# 04-Front_Panel_SFP.net
KiCad netlist of a schematic drawn in Altium Designer
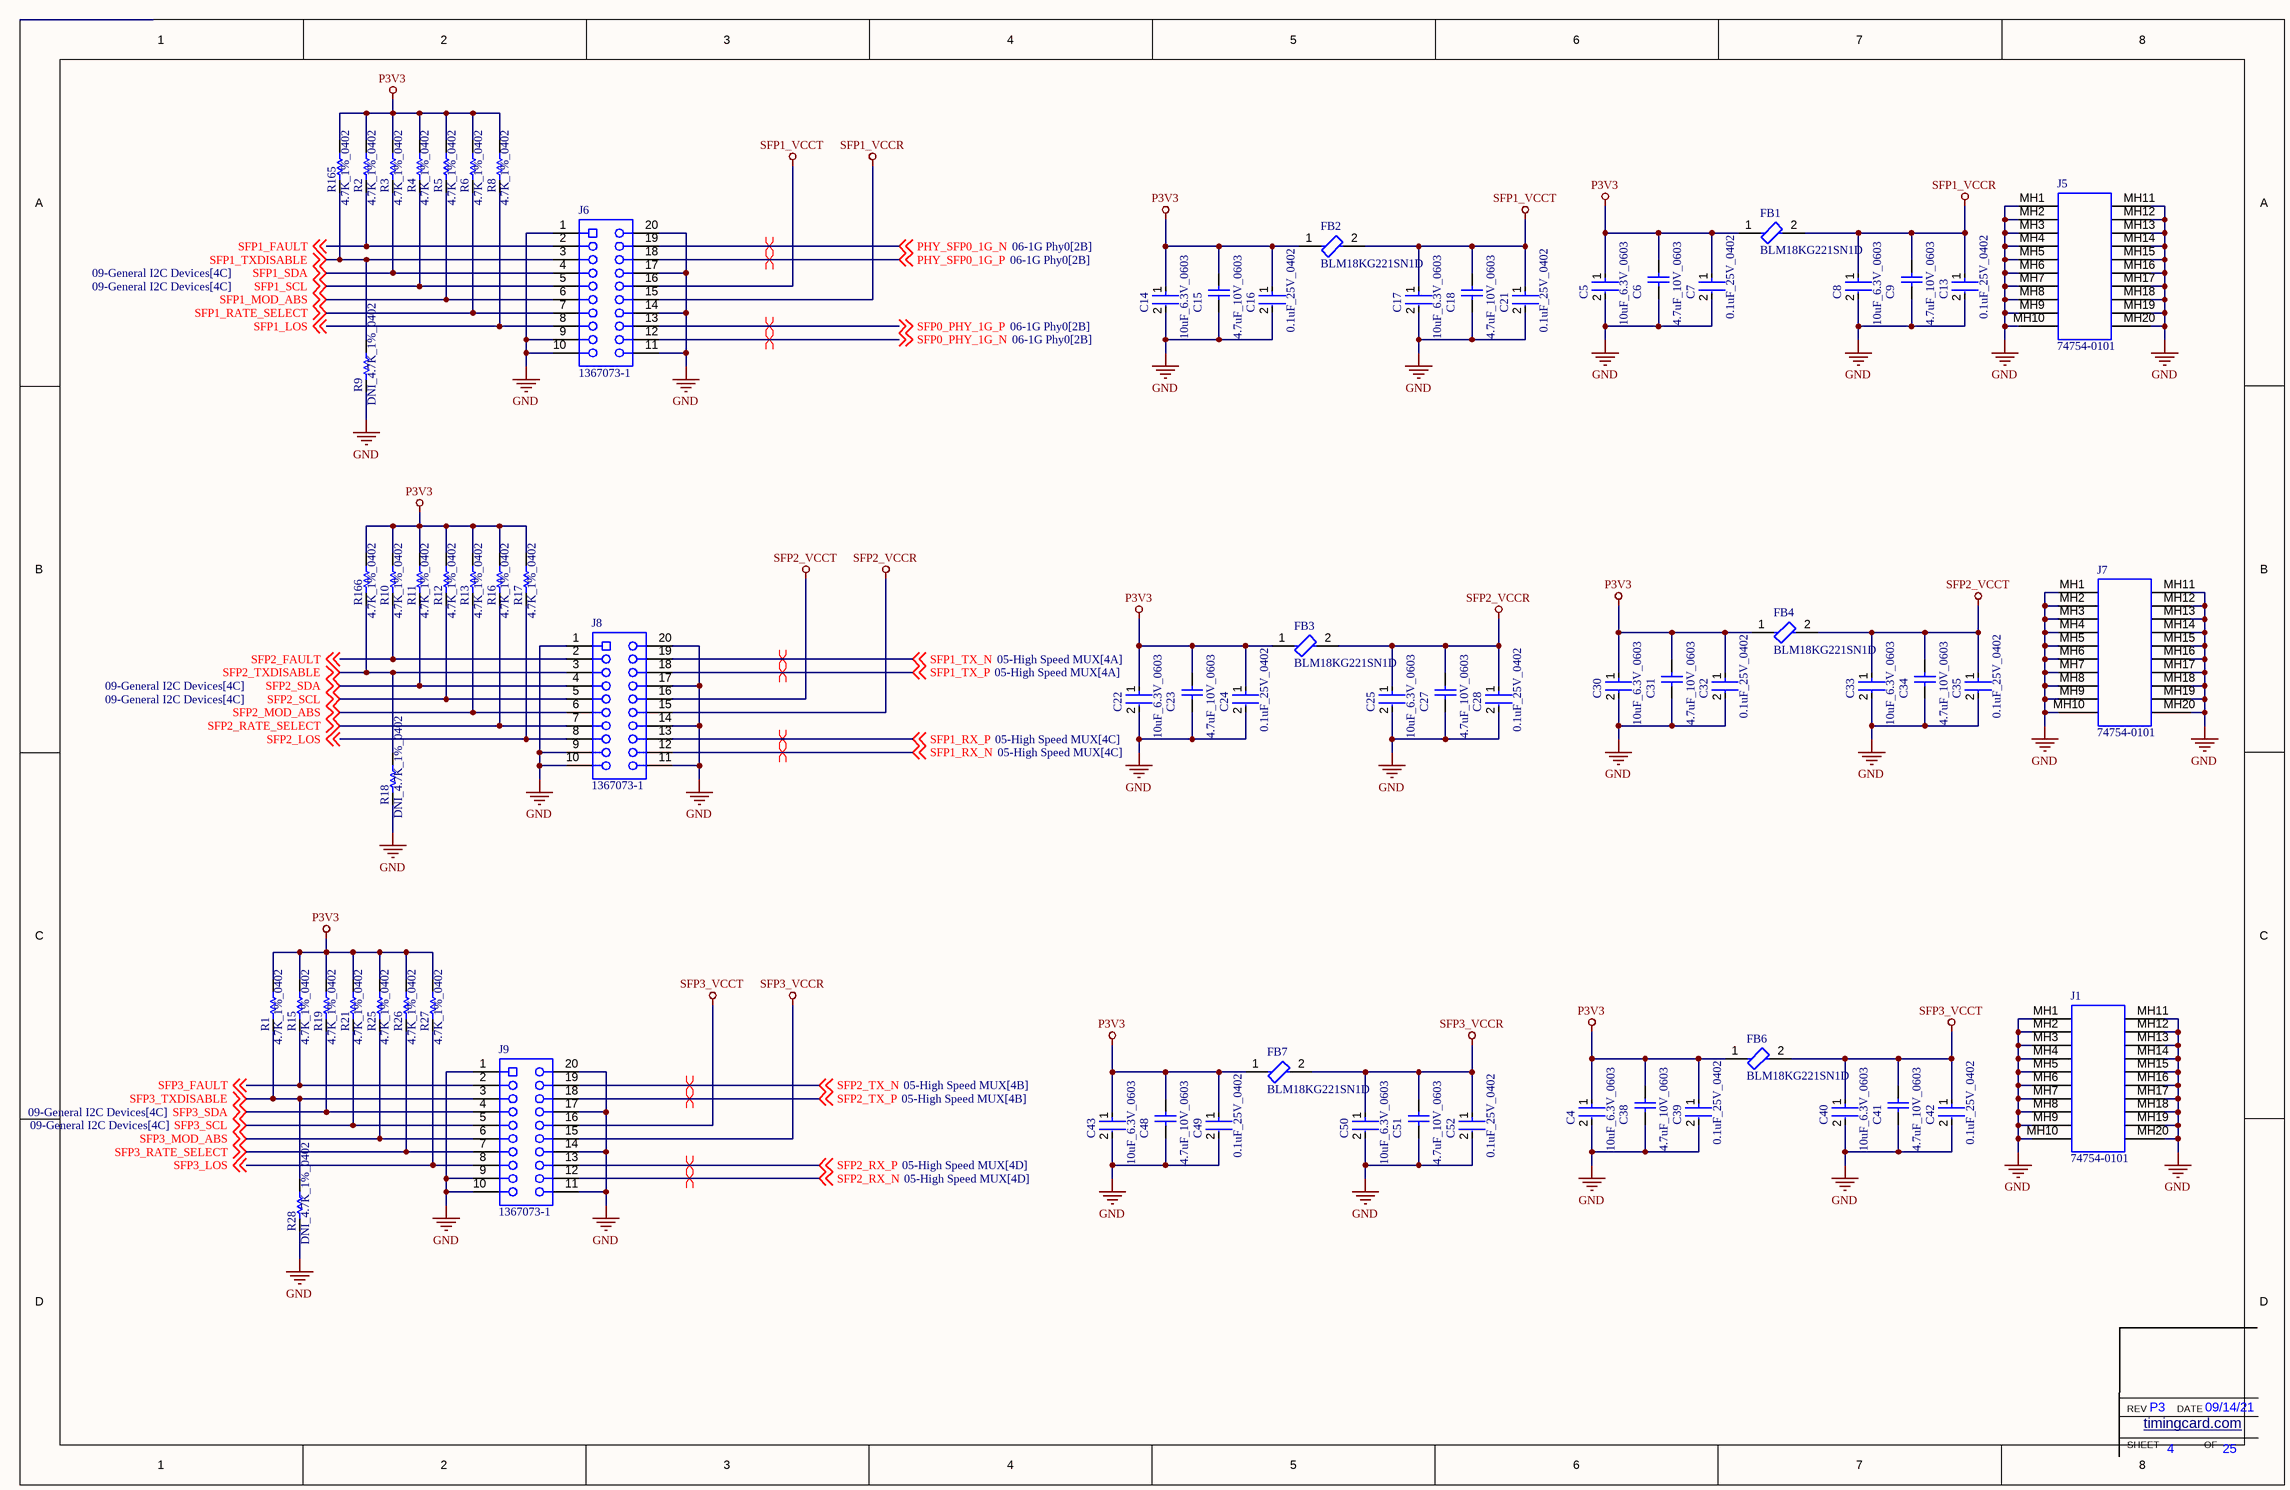
[diagram p0: 04-Front Panel SFP+.SchDoc]

(export (version "E")
  (design (tool "Eeschema 10.0.6"))
  (components
    (comp (ref "C4")
      (value "10uF_6.3V_0603")
      (footprint "FP-C0603C106M9PACTU-MFG")
      (description "CAP CER 10UF 6.3V X5R 0603")
      (fields
        (field (name "MANUFACTURER PART NUMBER") "C0603C106M9PACTU")
        (field (name "MANUFACTURER") "Kemet")
      )
      (libsource (lib "Altium Content Vault") (part "b4654b650e69147ec39a6b967a45e02"))
    )
    (comp (ref "C5")
      (value "10uF_6.3V_0603")
      (footprint "FP-C0603C106M9PACTU-MFG")
      (description "CAP CER 10UF 6.3V X5R 0603")
      (fields
        (field (name "MANUFACTURER PART NUMBER") "C0603C106M9PACTU")
        (field (name "MANUFACTURER") "Kemet")
      )
      (libsource (lib "Altium Content Vault") (part "b4654b650e69147ec39a6b967a45e02"))
    )
    (comp (ref "C6")
      (value "4.7uF_10V_0603")
      (footprint "CAPC1608X87X35NL15T15")
      (fields (field (name "PART NUMBER") "C0603C475K8PACTU") (field (name "MANUFACTURER") "Kemet"))
      (libsource (lib "Altium Content Vault") (part "CAP"))
    )
    (comp (ref "C7")
      (value "0.1uF_25V_0402")
      (footprint "FP-0402-L_1_0_1-W_0_5_0_1-IPC_C")
      (description "General Purpose Ceramic Capacitor, 0402, 100nF, 10%, X7R, 15%, 25V")
      (fields (field (name "VOLTAGE") "25V") (field (name "TOLERANCE") "10%"))
      (libsource (lib "Altium Content Vault") (part "b4654b650e69147ec39a6b967a45e02"))
    )
    (comp (ref "C8")
      (value "10uF_6.3V_0603")
      (footprint "FP-C0603C106M9PACTU-MFG")
      (description "CAP CER 10UF 6.3V X5R 0603")
      (fields
        (field (name "MANUFACTURER PART NUMBER") "C0603C106M9PACTU")
        (field (name "MANUFACTURER") "Kemet")
      )
      (libsource (lib "Altium Content Vault") (part "b4654b650e69147ec39a6b967a45e02"))
    )
    (comp (ref "C9")
      (value "4.7uF_10V_0603")
      (footprint "CAPC1608X87X35NL15T15")
      (fields (field (name "PART NUMBER") "C0603C475K8PACTU") (field (name "MANUFACTURER") "Kemet"))
      (libsource (lib "Altium Content Vault") (part "CAP"))
    )
    (comp (ref "C13")
      (value "0.1uF_25V_0402")
      (footprint "FP-0402-L_1_0_1-W_0_5_0_1-IPC_C")
      (description "General Purpose Ceramic Capacitor, 0402, 100nF, 10%, X7R, 15%, 25V")
      (fields (field (name "VOLTAGE") "25V") (field (name "TOLERANCE") "10%"))
      (libsource (lib "Altium Content Vault") (part "b4654b650e69147ec39a6b967a45e02"))
    )
    (comp (ref "C14")
      (value "10uF_6.3V_0603")
      (footprint "FP-C0603C106M9PACTU-MFG")
      (description "CAP CER 10UF 6.3V X5R 0603")
      (fields
        (field (name "MANUFACTURER PART NUMBER") "C0603C106M9PACTU")
        (field (name "MANUFACTURER") "Kemet")
      )
      (libsource (lib "Altium Content Vault") (part "b4654b650e69147ec39a6b967a45e02"))
    )
    (comp (ref "C15")
      (value "4.7uF_10V_0603")
      (footprint "CAPC1608X87X35NL15T15")
      (fields (field (name "PART NUMBER") "C0603C475K8PACTU") (field (name "MANUFACTURER") "Kemet"))
      (libsource (lib "Altium Content Vault") (part "CAP"))
    )
    (comp (ref "C16")
      (value "0.1uF_25V_0402")
      (footprint "FP-0402-L_1_0_1-W_0_5_0_1-IPC_C")
      (description "General Purpose Ceramic Capacitor, 0402, 100nF, 10%, X7R, 15%, 25V")
      (fields (field (name "VOLTAGE") "25V") (field (name "TOLERANCE") "10%"))
      (libsource (lib "Altium Content Vault") (part "b4654b650e69147ec39a6b967a45e02"))
    )
    (comp (ref "C17")
      (value "10uF_6.3V_0603")
      (footprint "FP-C0603C106M9PACTU-MFG")
      (description "CAP CER 10UF 6.3V X5R 0603")
      (fields
        (field (name "MANUFACTURER PART NUMBER") "C0603C106M9PACTU")
        (field (name "MANUFACTURER") "Kemet")
      )
      (libsource (lib "Altium Content Vault") (part "b4654b650e69147ec39a6b967a45e02"))
    )
    (comp (ref "C18")
      (value "4.7uF_10V_0603")
      (footprint "CAPC1608X87X35NL15T15")
      (fields (field (name "PART NUMBER") "C0603C475K8PACTU") (field (name "MANUFACTURER") "Kemet"))
      (libsource (lib "Altium Content Vault") (part "CAP"))
    )
    (comp (ref "C21")
      (value "0.1uF_25V_0402")
      (footprint "FP-0402-L_1_0_1-W_0_5_0_1-IPC_C")
      (description "General Purpose Ceramic Capacitor, 0402, 100nF, 10%, X7R, 15%, 25V")
      (fields (field (name "VOLTAGE") "25V") (field (name "TOLERANCE") "10%"))
      (libsource (lib "Altium Content Vault") (part "b4654b650e69147ec39a6b967a45e02"))
    )
    (comp (ref "C22")
      (value "10uF_6.3V_0603")
      (footprint "FP-C0603C106M9PACTU-MFG")
      (description "CAP CER 10UF 6.3V X5R 0603")
      (fields
        (field (name "MANUFACTURER PART NUMBER") "C0603C106M9PACTU")
        (field (name "MANUFACTURER") "Kemet")
      )
      (libsource (lib "Altium Content Vault") (part "b4654b650e69147ec39a6b967a45e02"))
    )
    (comp (ref "C23")
      (value "4.7uF_10V_0603")
      (footprint "CAPC1608X87X35NL15T15")
      (fields (field (name "PART NUMBER") "C0603C475K8PACTU") (field (name "MANUFACTURER") "Kemet"))
      (libsource (lib "Altium Content Vault") (part "CAP"))
    )
    (comp (ref "C24")
      (value "0.1uF_25V_0402")
      (footprint "FP-0402-L_1_0_1-W_0_5_0_1-IPC_C")
      (description "General Purpose Ceramic Capacitor, 0402, 100nF, 10%, X7R, 15%, 25V")
      (fields (field (name "VOLTAGE") "25V") (field (name "TOLERANCE") "10%"))
      (libsource (lib "Altium Content Vault") (part "b4654b650e69147ec39a6b967a45e02"))
    )
    (comp (ref "C25")
      (value "10uF_6.3V_0603")
      (footprint "FP-C0603C106M9PACTU-MFG")
      (description "CAP CER 10UF 6.3V X5R 0603")
      (fields
        (field (name "MANUFACTURER PART NUMBER") "C0603C106M9PACTU")
        (field (name "MANUFACTURER") "Kemet")
      )
      (libsource (lib "Altium Content Vault") (part "b4654b650e69147ec39a6b967a45e02"))
    )
    (comp (ref "C27")
      (value "4.7uF_10V_0603")
      (footprint "CAPC1608X87X35NL15T15")
      (fields (field (name "PART NUMBER") "C0603C475K8PACTU") (field (name "MANUFACTURER") "Kemet"))
      (libsource (lib "Altium Content Vault") (part "CAP"))
    )
    (comp (ref "C28")
      (value "0.1uF_25V_0402")
      (footprint "FP-0402-L_1_0_1-W_0_5_0_1-IPC_C")
      (description "General Purpose Ceramic Capacitor, 0402, 100nF, 10%, X7R, 15%, 25V")
      (fields (field (name "VOLTAGE") "25V") (field (name "TOLERANCE") "10%"))
      (libsource (lib "Altium Content Vault") (part "b4654b650e69147ec39a6b967a45e02"))
    )
    (comp (ref "C30")
      (value "10uF_6.3V_0603")
      (footprint "FP-C0603C106M9PACTU-MFG")
      (description "CAP CER 10UF 6.3V X5R 0603")
      (fields
        (field (name "MANUFACTURER PART NUMBER") "C0603C106M9PACTU")
        (field (name "MANUFACTURER") "Kemet")
      )
      (libsource (lib "Altium Content Vault") (part "b4654b650e69147ec39a6b967a45e02"))
    )
    (comp (ref "C31")
      (value "4.7uF_10V_0603")
      (footprint "CAPC1608X87X35NL15T15")
      (fields (field (name "PART NUMBER") "C0603C475K8PACTU") (field (name "MANUFACTURER") "Kemet"))
      (libsource (lib "Altium Content Vault") (part "CAP"))
    )
    (comp (ref "C32")
      (value "0.1uF_25V_0402")
      (footprint "FP-0402-L_1_0_1-W_0_5_0_1-IPC_C")
      (description "General Purpose Ceramic Capacitor, 0402, 100nF, 10%, X7R, 15%, 25V")
      (fields (field (name "VOLTAGE") "25V") (field (name "TOLERANCE") "10%"))
      (libsource (lib "Altium Content Vault") (part "b4654b650e69147ec39a6b967a45e02"))
    )
    (comp (ref "C33")
      (value "10uF_6.3V_0603")
      (footprint "FP-C0603C106M9PACTU-MFG")
      (description "CAP CER 10UF 6.3V X5R 0603")
      (fields
        (field (name "MANUFACTURER PART NUMBER") "C0603C106M9PACTU")
        (field (name "MANUFACTURER") "Kemet")
      )
      (libsource (lib "Altium Content Vault") (part "b4654b650e69147ec39a6b967a45e02"))
    )
    (comp (ref "C34")
      (value "4.7uF_10V_0603")
      (footprint "CAPC1608X87X35NL15T15")
      (fields (field (name "PART NUMBER") "C0603C475K8PACTU") (field (name "MANUFACTURER") "Kemet"))
      (libsource (lib "Altium Content Vault") (part "CAP"))
    )
    (comp (ref "C35")
      (value "0.1uF_25V_0402")
      (footprint "FP-0402-L_1_0_1-W_0_5_0_1-IPC_C")
      (description "General Purpose Ceramic Capacitor, 0402, 100nF, 10%, X7R, 15%, 25V")
      (fields (field (name "VOLTAGE") "25V") (field (name "TOLERANCE") "10%"))
      (libsource (lib "Altium Content Vault") (part "b4654b650e69147ec39a6b967a45e02"))
    )
    (comp (ref "C38")
      (value "4.7uF_10V_0603")
      (footprint "CAPC1608X87X35NL15T15")
      (fields (field (name "PART NUMBER") "C0603C475K8PACTU") (field (name "MANUFACTURER") "Kemet"))
      (libsource (lib "Altium Content Vault") (part "CAP"))
    )
    (comp (ref "C39")
      (value "0.1uF_25V_0402")
      (footprint "FP-0402-L_1_0_1-W_0_5_0_1-IPC_C")
      (description "General Purpose Ceramic Capacitor, 0402, 100nF, 10%, X7R, 15%, 25V")
      (fields (field (name "VOLTAGE") "25V") (field (name "TOLERANCE") "10%"))
      (libsource (lib "Altium Content Vault") (part "b4654b650e69147ec39a6b967a45e02"))
    )
    (comp (ref "C40")
      (value "10uF_6.3V_0603")
      (footprint "FP-C0603C106M9PACTU-MFG")
      (description "CAP CER 10UF 6.3V X5R 0603")
      (fields
        (field (name "MANUFACTURER PART NUMBER") "C0603C106M9PACTU")
        (field (name "MANUFACTURER") "Kemet")
      )
      (libsource (lib "Altium Content Vault") (part "b4654b650e69147ec39a6b967a45e02"))
    )
    (comp (ref "C41")
      (value "4.7uF_10V_0603")
      (footprint "CAPC1608X87X35NL15T15")
      (fields (field (name "PART NUMBER") "C0603C475K8PACTU") (field (name "MANUFACTURER") "Kemet"))
      (libsource (lib "Altium Content Vault") (part "CAP"))
    )
    (comp (ref "C42")
      (value "0.1uF_25V_0402")
      (footprint "FP-0402-L_1_0_1-W_0_5_0_1-IPC_C")
      (description "General Purpose Ceramic Capacitor, 0402, 100nF, 10%, X7R, 15%, 25V")
      (fields (field (name "VOLTAGE") "25V") (field (name "TOLERANCE") "10%"))
      (libsource (lib "Altium Content Vault") (part "b4654b650e69147ec39a6b967a45e02"))
    )
    (comp (ref "C43")
      (value "10uF_6.3V_0603")
      (footprint "FP-C0603C106M9PACTU-MFG")
      (description "CAP CER 10UF 6.3V X5R 0603")
      (fields
        (field (name "MANUFACTURER PART NUMBER") "C0603C106M9PACTU")
        (field (name "MANUFACTURER") "Kemet")
      )
      (libsource (lib "Altium Content Vault") (part "b4654b650e69147ec39a6b967a45e02"))
    )
    (comp (ref "C48")
      (value "4.7uF_10V_0603")
      (footprint "CAPC1608X87X35NL15T15")
      (fields (field (name "PART NUMBER") "C0603C475K8PACTU") (field (name "MANUFACTURER") "Kemet"))
      (libsource (lib "Altium Content Vault") (part "CAP"))
    )
    (comp (ref "C49")
      (value "0.1uF_25V_0402")
      (footprint "FP-0402-L_1_0_1-W_0_5_0_1-IPC_C")
      (description "General Purpose Ceramic Capacitor, 0402, 100nF, 10%, X7R, 15%, 25V")
      (fields (field (name "VOLTAGE") "25V") (field (name "TOLERANCE") "10%"))
      (libsource (lib "Altium Content Vault") (part "b4654b650e69147ec39a6b967a45e02"))
    )
    (comp (ref "C50")
      (value "10uF_6.3V_0603")
      (footprint "FP-C0603C106M9PACTU-MFG")
      (description "CAP CER 10UF 6.3V X5R 0603")
      (fields
        (field (name "MANUFACTURER PART NUMBER") "C0603C106M9PACTU")
        (field (name "MANUFACTURER") "Kemet")
      )
      (libsource (lib "Altium Content Vault") (part "b4654b650e69147ec39a6b967a45e02"))
    )
    (comp (ref "C51")
      (value "4.7uF_10V_0603")
      (footprint "CAPC1608X87X35NL15T15")
      (fields (field (name "PART NUMBER") "C0603C475K8PACTU") (field (name "MANUFACTURER") "Kemet"))
      (libsource (lib "Altium Content Vault") (part "CAP"))
    )
    (comp (ref "C52")
      (value "0.1uF_25V_0402")
      (footprint "FP-0402-L_1_0_1-W_0_5_0_1-IPC_C")
      (description "General Purpose Ceramic Capacitor, 0402, 100nF, 10%, X7R, 15%, 25V")
      (fields (field (name "VOLTAGE") "25V") (field (name "TOLERANCE") "10%"))
      (libsource (lib "Altium Content Vault") (part "b4654b650e69147ec39a6b967a45e02"))
    )
    (comp (ref "FB1")
      (value "BLM18KG221SN1D")
      (footprint "FP-BLM18-0_15-t0_8-IPC_B")
      (description "Chip Ferrite Bead, 0603, 220Ω @ 100MHz, 0.05Ω, 25%, 2.2A")
      (fields (field (name "TOLERANCE") "25%"))
      (libsource (lib "Altium Content Vault") (part "5f30dd21d616792df468990f7003faa"))
    )
    (comp (ref "FB2")
      (value "BLM18KG221SN1D")
      (footprint "FP-BLM18-0_15-t0_8-IPC_B")
      (description "Chip Ferrite Bead, 0603, 220Ω @ 100MHz, 0.05Ω, 25%, 2.2A")
      (fields (field (name "TOLERANCE") "25%"))
      (libsource (lib "Altium Content Vault") (part "5f30dd21d616792df468990f7003faa"))
    )
    (comp (ref "FB3")
      (value "BLM18KG221SN1D")
      (footprint "FP-BLM18-0_15-t0_8-IPC_B")
      (description "Chip Ferrite Bead, 0603, 220Ω @ 100MHz, 0.05Ω, 25%, 2.2A")
      (fields (field (name "TOLERANCE") "25%"))
      (libsource (lib "Altium Content Vault") (part "5f30dd21d616792df468990f7003faa"))
    )
    (comp (ref "FB4")
      (value "BLM18KG221SN1D")
      (footprint "FP-BLM18-0_15-t0_8-IPC_B")
      (description "Chip Ferrite Bead, 0603, 220Ω @ 100MHz, 0.05Ω, 25%, 2.2A")
      (fields (field (name "TOLERANCE") "25%"))
      (libsource (lib "Altium Content Vault") (part "5f30dd21d616792df468990f7003faa"))
    )
    (comp (ref "FB6")
      (value "BLM18KG221SN1D")
      (footprint "FP-BLM18-0_15-t0_8-IPC_B")
      (description "Chip Ferrite Bead, 0603, 220Ω @ 100MHz, 0.05Ω, 25%, 2.2A")
      (fields (field (name "TOLERANCE") "25%"))
      (libsource (lib "Altium Content Vault") (part "5f30dd21d616792df468990f7003faa"))
    )
    (comp (ref "FB7")
      (value "BLM18KG221SN1D")
      (footprint "FP-BLM18-0_15-t0_8-IPC_B")
      (description "Chip Ferrite Bead, 0603, 220Ω @ 100MHz, 0.05Ω, 25%, 2.2A")
      (fields (field (name "TOLERANCE") "25%"))
      (libsource (lib "Altium Content Vault") (part "5f30dd21d616792df468990f7003faa"))
    )
    (comp (ref "J1")
      (value "74754-0101")
      (footprint "MOLX-74754-0101_V")
      (description "SFP+ Cage, Single Port, Height 10.85 mm, Tail Height 3.05 mm, -40 to 85 degC, RoHS, Tray")
      (libsource (lib "Altium Content Vault") (part "MOLX-74754-0101"))
    )
    (comp (ref "J5")
      (value "74754-0101")
      (footprint "MOLX-74754-0101_V")
      (description "SFP+ Cage, Single Port, Height 10.85 mm, Tail Height 3.05 mm, -40 to 85 degC, RoHS, Tray")
      (libsource (lib "Altium Content Vault") (part "MOLX-74754-0101"))
    )
    (comp (ref "J6")
      (value "1367073-1")
      (footprint "TECO-1367073-1_V")
      (fields (field (name "MANUFACTURER") "TE Connectivity"))
      (libsource (lib "Altium Content Vault") (part "CN-2P-F-R20_B"))
    )
    (comp (ref "J7")
      (value "74754-0101")
      (footprint "MOLX-74754-0101_V")
      (description "SFP+ Cage, Single Port, Height 10.85 mm, Tail Height 3.05 mm, -40 to 85 degC, RoHS, Tray")
      (libsource (lib "Altium Content Vault") (part "MOLX-74754-0101"))
    )
    (comp (ref "J8")
      (value "1367073-1")
      (footprint "TECO-1367073-1_V")
      (fields (field (name "MANUFACTURER") "TE Connectivity"))
      (libsource (lib "Altium Content Vault") (part "CN-2P-F-R20_B"))
    )
    (comp (ref "J9")
      (value "1367073-1")
      (footprint "TECO-1367073-1_V")
      (fields (field (name "MANUFACTURER") "TE Connectivity"))
      (libsource (lib "Altium Content Vault") (part "CN-2P-F-R20_B"))
    )
    (comp (ref "R1")
      (value "4.7K_1%_0402")
      (footprint "RESC1005X40X25NL10T10")
      (fields (field (name "MANUFACTURER") "Bourns") (field (name "PART NUMBER") "CR0402-FX-4701GLF"))
      (libsource (lib "Altium Content Vault") (part "RES"))
    )
    (comp (ref "R2")
      (value "4.7K_1%_0402")
      (footprint "RESC1005X40X25NL10T10")
      (fields (field (name "MANUFACTURER") "Bourns") (field (name "PART NUMBER") "CR0402-FX-4701GLF"))
      (libsource (lib "Altium Content Vault") (part "RES"))
    )
    (comp (ref "R3")
      (value "4.7K_1%_0402")
      (footprint "RESC1005X40X25NL10T10")
      (fields (field (name "MANUFACTURER") "Bourns") (field (name "PART NUMBER") "CR0402-FX-4701GLF"))
      (libsource (lib "Altium Content Vault") (part "RES"))
    )
    (comp (ref "R4")
      (value "4.7K_1%_0402")
      (footprint "RESC1005X40X25NL10T10")
      (fields (field (name "MANUFACTURER") "Bourns") (field (name "PART NUMBER") "CR0402-FX-4701GLF"))
      (libsource (lib "Altium Content Vault") (part "RES"))
    )
    (comp (ref "R5")
      (value "4.7K_1%_0402")
      (footprint "RESC1005X40X25NL10T10")
      (fields (field (name "MANUFACTURER") "Bourns") (field (name "PART NUMBER") "CR0402-FX-4701GLF"))
      (libsource (lib "Altium Content Vault") (part "RES"))
    )
    (comp (ref "R6")
      (value "4.7K_1%_0402")
      (footprint "RESC1005X40X25NL10T10")
      (fields (field (name "MANUFACTURER") "Bourns") (field (name "PART NUMBER") "CR0402-FX-4701GLF"))
      (libsource (lib "Altium Content Vault") (part "RES"))
    )
    (comp (ref "R8")
      (value "4.7K_1%_0402")
      (footprint "RESC1005X40X25NL10T10")
      (fields (field (name "MANUFACTURER") "Bourns") (field (name "PART NUMBER") "CR0402-FX-4701GLF"))
      (libsource (lib "Altium Content Vault") (part "RES"))
    )
    (comp (ref "R9")
      (value "DNI_4.7K_1%_0402")
      (footprint "RESC1005X40X25NL10T10")
      (fields (field (name "MANUFACTURER") "Bourns") (field (name "PART NUMBER") "CR0402-FX-4701GLF"))
      (libsource (lib "Altium Content Vault") (part "RES"))
    )
    (comp (ref "R10")
      (value "4.7K_1%_0402")
      (footprint "RESC1005X40X25NL10T10")
      (fields (field (name "MANUFACTURER") "Bourns") (field (name "PART NUMBER") "CR0402-FX-4701GLF"))
      (libsource (lib "Altium Content Vault") (part "RES"))
    )
    (comp (ref "R11")
      (value "4.7K_1%_0402")
      (footprint "RESC1005X40X25NL10T10")
      (fields (field (name "MANUFACTURER") "Bourns") (field (name "PART NUMBER") "CR0402-FX-4701GLF"))
      (libsource (lib "Altium Content Vault") (part "RES"))
    )
    (comp (ref "R12")
      (value "4.7K_1%_0402")
      (footprint "RESC1005X40X25NL10T10")
      (fields (field (name "MANUFACTURER") "Bourns") (field (name "PART NUMBER") "CR0402-FX-4701GLF"))
      (libsource (lib "Altium Content Vault") (part "RES"))
    )
    (comp (ref "R13")
      (value "4.7K_1%_0402")
      (footprint "RESC1005X40X25NL10T10")
      (fields (field (name "MANUFACTURER") "Bourns") (field (name "PART NUMBER") "CR0402-FX-4701GLF"))
      (libsource (lib "Altium Content Vault") (part "RES"))
    )
    (comp (ref "R15")
      (value "4.7K_1%_0402")
      (footprint "RESC1005X40X25NL10T10")
      (fields (field (name "MANUFACTURER") "Bourns") (field (name "PART NUMBER") "CR0402-FX-4701GLF"))
      (libsource (lib "Altium Content Vault") (part "RES"))
    )
    (comp (ref "R16")
      (value "4.7K_1%_0402")
      (footprint "RESC1005X40X25NL10T10")
      (fields (field (name "MANUFACTURER") "Bourns") (field (name "PART NUMBER") "CR0402-FX-4701GLF"))
      (libsource (lib "Altium Content Vault") (part "RES"))
    )
    (comp (ref "R17")
      (value "4.7K_1%_0402")
      (footprint "RESC1005X40X25NL10T10")
      (fields (field (name "MANUFACTURER") "Bourns") (field (name "PART NUMBER") "CR0402-FX-4701GLF"))
      (libsource (lib "Altium Content Vault") (part "RES"))
    )
    (comp (ref "R18")
      (value "DNI_4.7K_1%_0402")
      (footprint "RESC1005X40X25NL10T10")
      (fields (field (name "MANUFACTURER") "Bourns") (field (name "PART NUMBER") "CR0402-FX-4701GLF"))
      (libsource (lib "Altium Content Vault") (part "RES"))
    )
    (comp (ref "R19")
      (value "4.7K_1%_0402")
      (footprint "RESC1005X40X25NL10T10")
      (fields (field (name "MANUFACTURER") "Bourns") (field (name "PART NUMBER") "CR0402-FX-4701GLF"))
      (libsource (lib "Altium Content Vault") (part "RES"))
    )
    (comp (ref "R21")
      (value "4.7K_1%_0402")
      (footprint "RESC1005X40X25NL10T10")
      (fields (field (name "MANUFACTURER") "Bourns") (field (name "PART NUMBER") "CR0402-FX-4701GLF"))
      (libsource (lib "Altium Content Vault") (part "RES"))
    )
    (comp (ref "R25")
      (value "4.7K_1%_0402")
      (footprint "RESC1005X40X25NL10T10")
      (fields (field (name "MANUFACTURER") "Bourns") (field (name "PART NUMBER") "CR0402-FX-4701GLF"))
      (libsource (lib "Altium Content Vault") (part "RES"))
    )
    (comp (ref "R26")
      (value "4.7K_1%_0402")
      (footprint "RESC1005X40X25NL10T10")
      (fields (field (name "MANUFACTURER") "Bourns") (field (name "PART NUMBER") "CR0402-FX-4701GLF"))
      (libsource (lib "Altium Content Vault") (part "RES"))
    )
    (comp (ref "R27")
      (value "4.7K_1%_0402")
      (footprint "RESC1005X40X25NL10T10")
      (fields (field (name "MANUFACTURER") "Bourns") (field (name "PART NUMBER") "CR0402-FX-4701GLF"))
      (libsource (lib "Altium Content Vault") (part "RES"))
    )
    (comp (ref "R28")
      (value "DNI_4.7K_1%_0402")
      (footprint "RESC1005X40X25NL10T10")
      (fields (field (name "MANUFACTURER") "Bourns") (field (name "PART NUMBER") "CR0402-FX-4701GLF"))
      (libsource (lib "Altium Content Vault") (part "RES"))
    )
    (comp (ref "R165")
      (value "4.7K_1%_0402")
      (footprint "RESC1005X40X25NL10T10")
      (fields (field (name "MANUFACTURER") "Bourns") (field (name "PART NUMBER") "CR0402-FX-4701GLF"))
      (libsource (lib "Altium Content Vault") (part "RES"))
    )
    (comp (ref "R166")
      (value "4.7K_1%_0402")
      (footprint "RESC1005X40X25NL10T10")
      (fields (field (name "MANUFACTURER") "Bourns") (field (name "PART NUMBER") "CR0402-FX-4701GLF"))
      (libsource (lib "Altium Content Vault") (part "RES"))
    )
  )
  (nets
    (net (code "1") (name "GND") (class "Default")
      (node (ref "C13") (pin "2") (pinfunction "2_2") (pintype "passive"))
      (node (ref "C14") (pin "2") (pinfunction "2_2") (pintype "passive"))
      (node (ref "C15") (pin "1") (pinfunction "1_1") (pintype "passive"))
      (node (ref "C16") (pin "2") (pinfunction "2_2") (pintype "passive"))
      (node (ref "C17") (pin "2") (pinfunction "2_2") (pintype "passive"))
      (node (ref "C18") (pin "1") (pinfunction "1_1") (pintype "passive"))
      (node (ref "C21") (pin "2") (pinfunction "2_2") (pintype "passive"))
      (node (ref "C22") (pin "2") (pinfunction "2_2") (pintype "passive"))
      (node (ref "C23") (pin "1") (pinfunction "1_1") (pintype "passive"))
      (node (ref "C24") (pin "2") (pinfunction "2_2") (pintype "passive"))
      (node (ref "C25") (pin "2") (pinfunction "2_2") (pintype "passive"))
      (node (ref "C27") (pin "1") (pinfunction "1_1") (pintype "passive"))
      (node (ref "C28") (pin "2") (pinfunction "2_2") (pintype "passive"))
      (node (ref "C30") (pin "2") (pinfunction "2_2") (pintype "passive"))
      (node (ref "C31") (pin "1") (pinfunction "1_1") (pintype "passive"))
      (node (ref "C32") (pin "2") (pinfunction "2_2") (pintype "passive"))
      (node (ref "C33") (pin "2") (pinfunction "2_2") (pintype "passive"))
      (node (ref "C34") (pin "1") (pinfunction "1_1") (pintype "passive"))
      (node (ref "C35") (pin "2") (pinfunction "2_2") (pintype "passive"))
      (node (ref "C38") (pin "1") (pinfunction "1_1") (pintype "passive"))
      (node (ref "C39") (pin "2") (pinfunction "2_2") (pintype "passive"))
      (node (ref "C4") (pin "2") (pinfunction "2_2") (pintype "passive"))
      (node (ref "C40") (pin "2") (pinfunction "2_2") (pintype "passive"))
      (node (ref "C41") (pin "1") (pinfunction "1_1") (pintype "passive"))
      (node (ref "C42") (pin "2") (pinfunction "2_2") (pintype "passive"))
      (node (ref "C43") (pin "2") (pinfunction "2_2") (pintype "passive"))
      (node (ref "C48") (pin "1") (pinfunction "1_1") (pintype "passive"))
      (node (ref "C49") (pin "2") (pinfunction "2_2") (pintype "passive"))
      (node (ref "C5") (pin "2") (pinfunction "2_2") (pintype "passive"))
      (node (ref "C50") (pin "2") (pinfunction "2_2") (pintype "passive"))
      (node (ref "C51") (pin "1") (pinfunction "1_1") (pintype "passive"))
      (node (ref "C52") (pin "2") (pinfunction "2_2") (pintype "passive"))
      (node (ref "C6") (pin "1") (pinfunction "1_1") (pintype "passive"))
      (node (ref "C7") (pin "2") (pinfunction "2_2") (pintype "passive"))
      (node (ref "C8") (pin "2") (pinfunction "2_2") (pintype "passive"))
      (node (ref "C9") (pin "1") (pinfunction "1_1") (pintype "passive"))
      (node (ref "J1") (pin "MH1") (pinfunction "MH1_MH1") (pintype "passive"))
      (node (ref "J1") (pin "MH10") (pinfunction "MH10_MH10") (pintype "passive"))
      (node (ref "J1") (pin "MH11") (pinfunction "MH11_MH11") (pintype "passive"))
      (node (ref "J1") (pin "MH12") (pinfunction "MH12_MH12") (pintype "passive"))
      (node (ref "J1") (pin "MH13") (pinfunction "MH13_MH13") (pintype "passive"))
      (node (ref "J1") (pin "MH14") (pinfunction "MH14_MH14") (pintype "passive"))
      (node (ref "J1") (pin "MH15") (pinfunction "MH15_MH15") (pintype "passive"))
      (node (ref "J1") (pin "MH16") (pinfunction "MH16_MH16") (pintype "passive"))
      (node (ref "J1") (pin "MH17") (pinfunction "MH17_MH17") (pintype "passive"))
      (node (ref "J1") (pin "MH18") (pinfunction "MH18_MH18") (pintype "passive"))
      (node (ref "J1") (pin "MH19") (pinfunction "MH19_MH19") (pintype "passive"))
      (node (ref "J1") (pin "MH2") (pinfunction "MH2_MH2") (pintype "passive"))
      (node (ref "J1") (pin "MH20") (pinfunction "MH20_MH20") (pintype "passive"))
      (node (ref "J1") (pin "MH3") (pinfunction "MH3_MH3") (pintype "passive"))
      (node (ref "J1") (pin "MH4") (pinfunction "MH4_MH4") (pintype "passive"))
      (node (ref "J1") (pin "MH5") (pinfunction "MH5_MH5") (pintype "passive"))
      (node (ref "J1") (pin "MH6") (pinfunction "MH6_MH6") (pintype "passive"))
      (node (ref "J1") (pin "MH7") (pinfunction "MH7_MH7") (pintype "passive"))
      (node (ref "J1") (pin "MH8") (pinfunction "MH8_MH8") (pintype "passive"))
      (node (ref "J1") (pin "MH9") (pinfunction "MH9_MH9") (pintype "passive"))
      (node (ref "J5") (pin "MH1") (pinfunction "MH1_MH1") (pintype "passive"))
      (node (ref "J5") (pin "MH10") (pinfunction "MH10_MH10") (pintype "passive"))
      (node (ref "J5") (pin "MH11") (pinfunction "MH11_MH11") (pintype "passive"))
      (node (ref "J5") (pin "MH12") (pinfunction "MH12_MH12") (pintype "passive"))
      (node (ref "J5") (pin "MH13") (pinfunction "MH13_MH13") (pintype "passive"))
      (node (ref "J5") (pin "MH14") (pinfunction "MH14_MH14") (pintype "passive"))
      (node (ref "J5") (pin "MH15") (pinfunction "MH15_MH15") (pintype "passive"))
      (node (ref "J5") (pin "MH16") (pinfunction "MH16_MH16") (pintype "passive"))
      (node (ref "J5") (pin "MH17") (pinfunction "MH17_MH17") (pintype "passive"))
      (node (ref "J5") (pin "MH18") (pinfunction "MH18_MH18") (pintype "passive"))
      (node (ref "J5") (pin "MH19") (pinfunction "MH19_MH19") (pintype "passive"))
      (node (ref "J5") (pin "MH2") (pinfunction "MH2_MH2") (pintype "passive"))
      (node (ref "J5") (pin "MH20") (pinfunction "MH20_MH20") (pintype "passive"))
      (node (ref "J5") (pin "MH3") (pinfunction "MH3_MH3") (pintype "passive"))
      (node (ref "J5") (pin "MH4") (pinfunction "MH4_MH4") (pintype "passive"))
      (node (ref "J5") (pin "MH5") (pinfunction "MH5_MH5") (pintype "passive"))
      (node (ref "J5") (pin "MH6") (pinfunction "MH6_MH6") (pintype "passive"))
      (node (ref "J5") (pin "MH7") (pinfunction "MH7_MH7") (pintype "passive"))
      (node (ref "J5") (pin "MH8") (pinfunction "MH8_MH8") (pintype "passive"))
      (node (ref "J5") (pin "MH9") (pinfunction "MH9_MH9") (pintype "passive"))
      (node (ref "J6") (pin "1") (pinfunction "1_1") (pintype "passive"))
      (node (ref "J6") (pin "10") (pinfunction "10_10") (pintype "passive"))
      (node (ref "J6") (pin "11") (pinfunction "11_11") (pintype "passive"))
      (node (ref "J6") (pin "14") (pinfunction "14_14") (pintype "passive"))
      (node (ref "J6") (pin "17") (pinfunction "17_17") (pintype "passive"))
      (node (ref "J6") (pin "20") (pinfunction "20_20") (pintype "passive"))
      (node (ref "J6") (pin "9") (pinfunction "9_9") (pintype "passive"))
      (node (ref "J7") (pin "MH1") (pinfunction "MH1_MH1") (pintype "passive"))
      (node (ref "J7") (pin "MH10") (pinfunction "MH10_MH10") (pintype "passive"))
      (node (ref "J7") (pin "MH11") (pinfunction "MH11_MH11") (pintype "passive"))
      (node (ref "J7") (pin "MH12") (pinfunction "MH12_MH12") (pintype "passive"))
      (node (ref "J7") (pin "MH13") (pinfunction "MH13_MH13") (pintype "passive"))
      (node (ref "J7") (pin "MH14") (pinfunction "MH14_MH14") (pintype "passive"))
      (node (ref "J7") (pin "MH15") (pinfunction "MH15_MH15") (pintype "passive"))
      (node (ref "J7") (pin "MH16") (pinfunction "MH16_MH16") (pintype "passive"))
      (node (ref "J7") (pin "MH17") (pinfunction "MH17_MH17") (pintype "passive"))
      (node (ref "J7") (pin "MH18") (pinfunction "MH18_MH18") (pintype "passive"))
      (node (ref "J7") (pin "MH19") (pinfunction "MH19_MH19") (pintype "passive"))
      (node (ref "J7") (pin "MH2") (pinfunction "MH2_MH2") (pintype "passive"))
      (node (ref "J7") (pin "MH20") (pinfunction "MH20_MH20") (pintype "passive"))
      (node (ref "J7") (pin "MH3") (pinfunction "MH3_MH3") (pintype "passive"))
      (node (ref "J7") (pin "MH4") (pinfunction "MH4_MH4") (pintype "passive"))
      (node (ref "J7") (pin "MH5") (pinfunction "MH5_MH5") (pintype "passive"))
      (node (ref "J7") (pin "MH6") (pinfunction "MH6_MH6") (pintype "passive"))
      (node (ref "J7") (pin "MH7") (pinfunction "MH7_MH7") (pintype "passive"))
      (node (ref "J7") (pin "MH8") (pinfunction "MH8_MH8") (pintype "passive"))
      (node (ref "J7") (pin "MH9") (pinfunction "MH9_MH9") (pintype "passive"))
      (node (ref "J8") (pin "1") (pinfunction "1_1") (pintype "passive"))
      (node (ref "J8") (pin "10") (pinfunction "10_10") (pintype "passive"))
      (node (ref "J8") (pin "11") (pinfunction "11_11") (pintype "passive"))
      (node (ref "J8") (pin "14") (pinfunction "14_14") (pintype "passive"))
      (node (ref "J8") (pin "17") (pinfunction "17_17") (pintype "passive"))
      (node (ref "J8") (pin "20") (pinfunction "20_20") (pintype "passive"))
      (node (ref "J8") (pin "9") (pinfunction "9_9") (pintype "passive"))
      (node (ref "J9") (pin "1") (pinfunction "1_1") (pintype "passive"))
      (node (ref "J9") (pin "10") (pinfunction "10_10") (pintype "passive"))
      (node (ref "J9") (pin "11") (pinfunction "11_11") (pintype "passive"))
      (node (ref "J9") (pin "14") (pinfunction "14_14") (pintype "passive"))
      (node (ref "J9") (pin "17") (pinfunction "17_17") (pintype "passive"))
      (node (ref "J9") (pin "20") (pinfunction "20_20") (pintype "passive"))
      (node (ref "J9") (pin "9") (pinfunction "9_9") (pintype "passive"))
      (node (ref "R18") (pin "2") (pinfunction "2_2") (pintype "passive"))
      (node (ref "R28") (pin "2") (pinfunction "2_2") (pintype "passive"))
      (node (ref "R9") (pin "2") (pinfunction "2_2") (pintype "passive"))
    )
    (net (code "2") (name "P3V3") (class "Default")
      (node (ref "C14") (pin "1") (pinfunction "1_1") (pintype "passive"))
      (node (ref "C15") (pin "2") (pinfunction "2_2") (pintype "passive"))
      (node (ref "C16") (pin "1") (pinfunction "1_1") (pintype "passive"))
      (node (ref "C22") (pin "1") (pinfunction "1_1") (pintype "passive"))
      (node (ref "C23") (pin "2") (pinfunction "2_2") (pintype "passive"))
      (node (ref "C24") (pin "1") (pinfunction "1_1") (pintype "passive"))
      (node (ref "C30") (pin "1") (pinfunction "1_1") (pintype "passive"))
      (node (ref "C31") (pin "2") (pinfunction "2_2") (pintype "passive"))
      (node (ref "C32") (pin "1") (pinfunction "1_1") (pintype "passive"))
      (node (ref "C38") (pin "2") (pinfunction "2_2") (pintype "passive"))
      (node (ref "C39") (pin "1") (pinfunction "1_1") (pintype "passive"))
      (node (ref "C4") (pin "1") (pinfunction "1_1") (pintype "passive"))
      (node (ref "C43") (pin "1") (pinfunction "1_1") (pintype "passive"))
      (node (ref "C48") (pin "2") (pinfunction "2_2") (pintype "passive"))
      (node (ref "C49") (pin "1") (pinfunction "1_1") (pintype "passive"))
      (node (ref "C5") (pin "1") (pinfunction "1_1") (pintype "passive"))
      (node (ref "C6") (pin "2") (pinfunction "2_2") (pintype "passive"))
      (node (ref "C7") (pin "1") (pinfunction "1_1") (pintype "passive"))
      (node (ref "FB1") (pin "1") (pinfunction "1_1") (pintype "passive"))
      (node (ref "FB2") (pin "1") (pinfunction "1_1") (pintype "passive"))
      (node (ref "FB3") (pin "1") (pinfunction "1_1") (pintype "passive"))
      (node (ref "FB4") (pin "1") (pinfunction "1_1") (pintype "passive"))
      (node (ref "FB6") (pin "1") (pinfunction "1_1") (pintype "passive"))
      (node (ref "FB7") (pin "1") (pinfunction "1_1") (pintype "passive"))
      (node (ref "R1") (pin "1") (pinfunction "1_1") (pintype "passive"))
      (node (ref "R10") (pin "1") (pinfunction "1_1") (pintype "passive"))
      (node (ref "R11") (pin "1") (pinfunction "1_1") (pintype "passive"))
      (node (ref "R12") (pin "1") (pinfunction "1_1") (pintype "passive"))
      (node (ref "R13") (pin "1") (pinfunction "1_1") (pintype "passive"))
      (node (ref "R15") (pin "1") (pinfunction "1_1") (pintype "passive"))
      (node (ref "R16") (pin "1") (pinfunction "1_1") (pintype "passive"))
      (node (ref "R165") (pin "1") (pinfunction "1_1") (pintype "passive"))
      (node (ref "R166") (pin "1") (pinfunction "1_1") (pintype "passive"))
      (node (ref "R17") (pin "1") (pinfunction "1_1") (pintype "passive"))
      (node (ref "R19") (pin "1") (pinfunction "1_1") (pintype "passive"))
      (node (ref "R2") (pin "1") (pinfunction "1_1") (pintype "passive"))
      (node (ref "R21") (pin "1") (pinfunction "1_1") (pintype "passive"))
      (node (ref "R25") (pin "1") (pinfunction "1_1") (pintype "passive"))
      (node (ref "R26") (pin "1") (pinfunction "1_1") (pintype "passive"))
      (node (ref "R27") (pin "1") (pinfunction "1_1") (pintype "passive"))
      (node (ref "R3") (pin "1") (pinfunction "1_1") (pintype "passive"))
      (node (ref "R4") (pin "1") (pinfunction "1_1") (pintype "passive"))
      (node (ref "R5") (pin "1") (pinfunction "1_1") (pintype "passive"))
      (node (ref "R6") (pin "1") (pinfunction "1_1") (pintype "passive"))
      (node (ref "R8") (pin "1") (pinfunction "1_1") (pintype "passive"))
    )
    (net (code "3") (name "PHY_SFP0_1G_N") (class "Default")
      (node (ref "J6") (pin "19") (pinfunction "19_19") (pintype "passive"))
    )
    (net (code "4") (name "PHY_SFP0_1G_P") (class "Default")
      (node (ref "J6") (pin "18") (pinfunction "18_18") (pintype "passive"))
    )
    (net (code "5") (name "SFP0_PHY_1G_N") (class "Default")
      (node (ref "J6") (pin "12") (pinfunction "12_12") (pintype "passive"))
    )
    (net (code "6") (name "SFP0_PHY_1G_P") (class "Default")
      (node (ref "J6") (pin "13") (pinfunction "13_13") (pintype "passive"))
    )
    (net (code "7") (name "SFP1_FAULT") (class "Default")
      (node (ref "J6") (pin "2") (pinfunction "2_2") (pintype "passive"))
      (node (ref "R2") (pin "2") (pinfunction "2_2") (pintype "passive"))
    )
    (net (code "8") (name "SFP1_LOS") (class "Default")
      (node (ref "J6") (pin "8") (pinfunction "8_8") (pintype "passive"))
      (node (ref "R8") (pin "2") (pinfunction "2_2") (pintype "passive"))
    )
    (net (code "9") (name "SFP1_MOD_ABS") (class "Default")
      (node (ref "J6") (pin "6") (pinfunction "6_6") (pintype "passive"))
      (node (ref "R5") (pin "2") (pinfunction "2_2") (pintype "passive"))
    )
    (net (code "10") (name "SFP1_RATE_SELECT") (class "Default")
      (node (ref "J6") (pin "7") (pinfunction "7_7") (pintype "passive"))
      (node (ref "R6") (pin "2") (pinfunction "2_2") (pintype "passive"))
    )
    (net (code "11") (name "SFP1_RX_N") (class "Default")
      (node (ref "J8") (pin "12") (pinfunction "12_12") (pintype "passive"))
    )
    (net (code "12") (name "SFP1_RX_P") (class "Default")
      (node (ref "J8") (pin "13") (pinfunction "13_13") (pintype "passive"))
    )
    (net (code "13") (name "SFP1_SCL") (class "Default")
      (node (ref "J6") (pin "5") (pinfunction "5_5") (pintype "passive"))
      (node (ref "R4") (pin "2") (pinfunction "2_2") (pintype "passive"))
    )
    (net (code "14") (name "SFP1_SDA") (class "Default")
      (node (ref "J6") (pin "4") (pinfunction "4_4") (pintype "passive"))
      (node (ref "R3") (pin "2") (pinfunction "2_2") (pintype "passive"))
    )
    (net (code "15") (name "SFP1_TXDISABLE") (class "Default")
      (node (ref "J6") (pin "3") (pinfunction "3_3") (pintype "passive"))
      (node (ref "R165") (pin "2") (pinfunction "2_2") (pintype "passive"))
      (node (ref "R9") (pin "1") (pinfunction "1_1") (pintype "passive"))
    )
    (net (code "16") (name "SFP1_TX_N") (class "Default")
      (node (ref "J8") (pin "19") (pinfunction "19_19") (pintype "passive"))
    )
    (net (code "17") (name "SFP1_TX_P") (class "Default")
      (node (ref "J8") (pin "18") (pinfunction "18_18") (pintype "passive"))
    )
    (net (code "18") (name "SFP1_VCCR") (class "Default")
      (node (ref "C13") (pin "1") (pinfunction "1_1") (pintype "passive"))
      (node (ref "C8") (pin "1") (pinfunction "1_1") (pintype "passive"))
      (node (ref "C9") (pin "2") (pinfunction "2_2") (pintype "passive"))
      (node (ref "FB1") (pin "2") (pinfunction "2_2") (pintype "passive"))
      (node (ref "J6") (pin "15") (pinfunction "15_15") (pintype "passive"))
    )
    (net (code "19") (name "SFP1_VCCT") (class "Default")
      (node (ref "C17") (pin "1") (pinfunction "1_1") (pintype "passive"))
      (node (ref "C18") (pin "2") (pinfunction "2_2") (pintype "passive"))
      (node (ref "C21") (pin "1") (pinfunction "1_1") (pintype "passive"))
      (node (ref "FB2") (pin "2") (pinfunction "2_2") (pintype "passive"))
      (node (ref "J6") (pin "16") (pinfunction "16_16") (pintype "passive"))
    )
    (net (code "20") (name "SFP2_FAULT") (class "Default")
      (node (ref "J8") (pin "2") (pinfunction "2_2") (pintype "passive"))
      (node (ref "R10") (pin "2") (pinfunction "2_2") (pintype "passive"))
    )
    (net (code "21") (name "SFP2_LOS") (class "Default")
      (node (ref "J8") (pin "8") (pinfunction "8_8") (pintype "passive"))
      (node (ref "R17") (pin "2") (pinfunction "2_2") (pintype "passive"))
    )
    (net (code "22") (name "SFP2_MOD_ABS") (class "Default")
      (node (ref "J8") (pin "6") (pinfunction "6_6") (pintype "passive"))
      (node (ref "R13") (pin "2") (pinfunction "2_2") (pintype "passive"))
    )
    (net (code "23") (name "SFP2_RATE_SELECT") (class "Default")
      (node (ref "J8") (pin "7") (pinfunction "7_7") (pintype "passive"))
      (node (ref "R16") (pin "2") (pinfunction "2_2") (pintype "passive"))
    )
    (net (code "24") (name "SFP2_RX_N") (class "Default")
      (node (ref "J9") (pin "12") (pinfunction "12_12") (pintype "passive"))
    )
    (net (code "25") (name "SFP2_RX_P") (class "Default")
      (node (ref "J9") (pin "13") (pinfunction "13_13") (pintype "passive"))
    )
    (net (code "26") (name "SFP2_SCL") (class "Default")
      (node (ref "J8") (pin "5") (pinfunction "5_5") (pintype "passive"))
      (node (ref "R12") (pin "2") (pinfunction "2_2") (pintype "passive"))
    )
    (net (code "27") (name "SFP2_SDA") (class "Default")
      (node (ref "J8") (pin "4") (pinfunction "4_4") (pintype "passive"))
      (node (ref "R11") (pin "2") (pinfunction "2_2") (pintype "passive"))
    )
    (net (code "28") (name "SFP2_TXDISABLE") (class "Default")
      (node (ref "J8") (pin "3") (pinfunction "3_3") (pintype "passive"))
      (node (ref "R166") (pin "2") (pinfunction "2_2") (pintype "passive"))
      (node (ref "R18") (pin "1") (pinfunction "1_1") (pintype "passive"))
    )
    (net (code "29") (name "SFP2_TX_N") (class "Default")
      (node (ref "J9") (pin "19") (pinfunction "19_19") (pintype "passive"))
    )
    (net (code "30") (name "SFP2_TX_P") (class "Default")
      (node (ref "J9") (pin "18") (pinfunction "18_18") (pintype "passive"))
    )
    (net (code "31") (name "SFP2_VCCR") (class "Default")
      (node (ref "C25") (pin "1") (pinfunction "1_1") (pintype "passive"))
      (node (ref "C27") (pin "2") (pinfunction "2_2") (pintype "passive"))
      (node (ref "C28") (pin "1") (pinfunction "1_1") (pintype "passive"))
      (node (ref "FB3") (pin "2") (pinfunction "2_2") (pintype "passive"))
      (node (ref "J8") (pin "15") (pinfunction "15_15") (pintype "passive"))
    )
    (net (code "32") (name "SFP2_VCCT") (class "Default")
      (node (ref "C33") (pin "1") (pinfunction "1_1") (pintype "passive"))
      (node (ref "C34") (pin "2") (pinfunction "2_2") (pintype "passive"))
      (node (ref "C35") (pin "1") (pinfunction "1_1") (pintype "passive"))
      (node (ref "FB4") (pin "2") (pinfunction "2_2") (pintype "passive"))
      (node (ref "J8") (pin "16") (pinfunction "16_16") (pintype "passive"))
    )
    (net (code "33") (name "SFP3_FAULT") (class "Default")
      (node (ref "J9") (pin "2") (pinfunction "2_2") (pintype "passive"))
      (node (ref "R15") (pin "2") (pinfunction "2_2") (pintype "passive"))
    )
    (net (code "34") (name "SFP3_LOS") (class "Default")
      (node (ref "J9") (pin "8") (pinfunction "8_8") (pintype "passive"))
      (node (ref "R27") (pin "2") (pinfunction "2_2") (pintype "passive"))
    )
    (net (code "35") (name "SFP3_MOD_ABS") (class "Default")
      (node (ref "J9") (pin "6") (pinfunction "6_6") (pintype "passive"))
      (node (ref "R25") (pin "2") (pinfunction "2_2") (pintype "passive"))
    )
    (net (code "36") (name "SFP3_RATE_SELECT") (class "Default")
      (node (ref "J9") (pin "7") (pinfunction "7_7") (pintype "passive"))
      (node (ref "R26") (pin "2") (pinfunction "2_2") (pintype "passive"))
    )
    (net (code "37") (name "SFP3_SCL") (class "Default")
      (node (ref "J9") (pin "5") (pinfunction "5_5") (pintype "passive"))
      (node (ref "R21") (pin "2") (pinfunction "2_2") (pintype "passive"))
    )
    (net (code "38") (name "SFP3_SDA") (class "Default")
      (node (ref "J9") (pin "4") (pinfunction "4_4") (pintype "passive"))
      (node (ref "R19") (pin "2") (pinfunction "2_2") (pintype "passive"))
    )
    (net (code "39") (name "SFP3_TXDISABLE") (class "Default")
      (node (ref "J9") (pin "3") (pinfunction "3_3") (pintype "passive"))
      (node (ref "R1") (pin "2") (pinfunction "2_2") (pintype "passive"))
      (node (ref "R28") (pin "1") (pinfunction "1_1") (pintype "passive"))
    )
    (net (code "40") (name "SFP3_VCCR") (class "Default")
      (node (ref "C50") (pin "1") (pinfunction "1_1") (pintype "passive"))
      (node (ref "C51") (pin "2") (pinfunction "2_2") (pintype "passive"))
      (node (ref "C52") (pin "1") (pinfunction "1_1") (pintype "passive"))
      (node (ref "FB7") (pin "2") (pinfunction "2_2") (pintype "passive"))
      (node (ref "J9") (pin "15") (pinfunction "15_15") (pintype "passive"))
    )
    (net (code "41") (name "SFP3_VCCT") (class "Default")
      (node (ref "C40") (pin "1") (pinfunction "1_1") (pintype "passive"))
      (node (ref "C41") (pin "2") (pinfunction "2_2") (pintype "passive"))
      (node (ref "C42") (pin "1") (pinfunction "1_1") (pintype "passive"))
      (node (ref "FB6") (pin "2") (pinfunction "2_2") (pintype "passive"))
      (node (ref "J9") (pin "16") (pinfunction "16_16") (pintype "passive"))
    )
  )
)
